# DISPLAY.net
KiCad netlist of a schematic drawn in Altium Designer
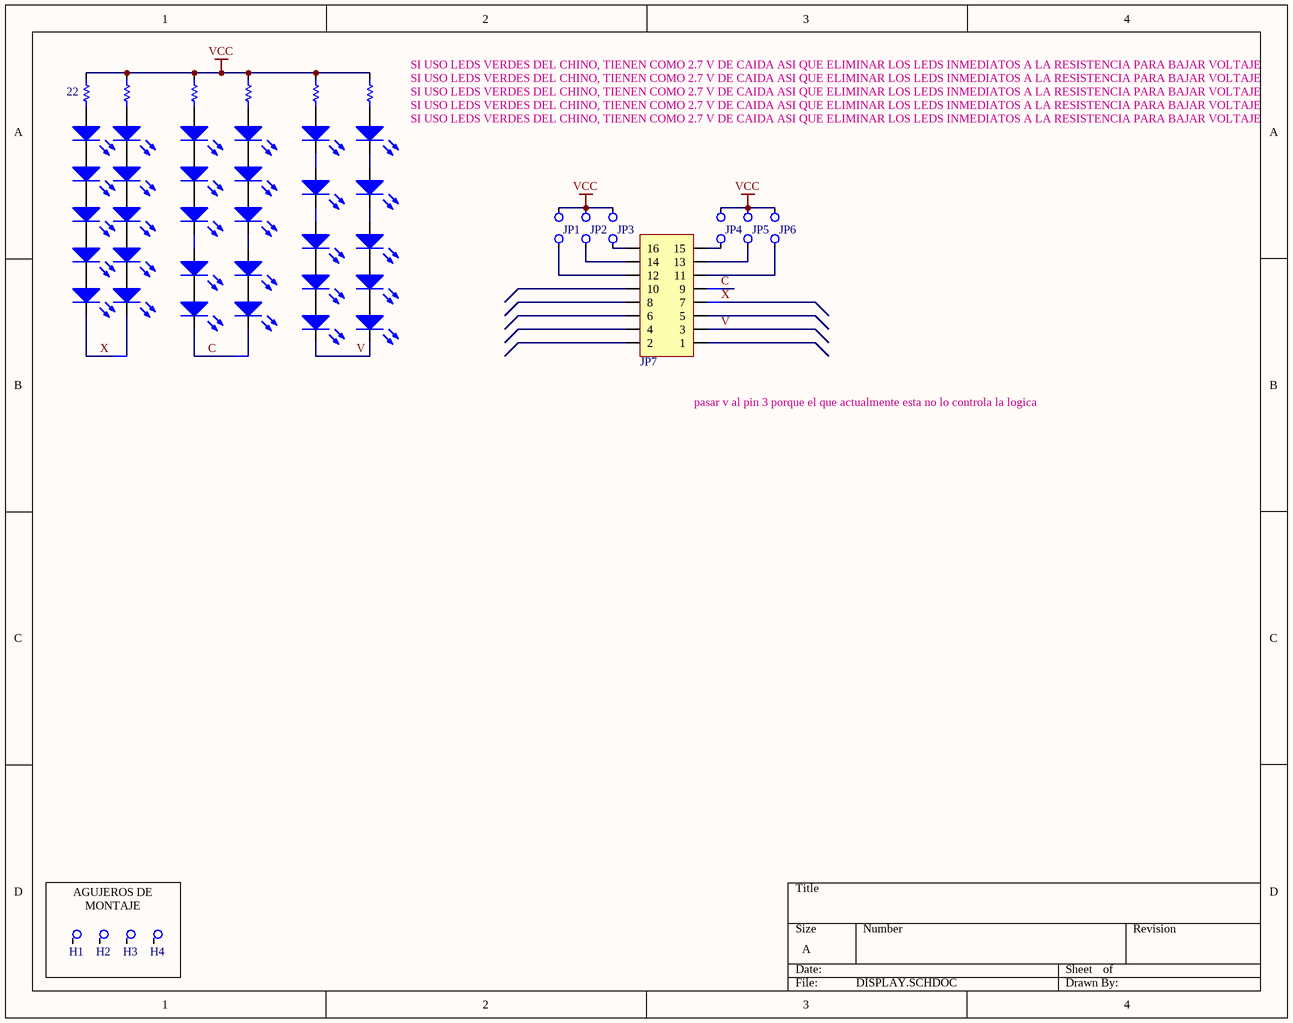
[diagram p0: DISPLAY.SCHDOC]

(export (version "E")
  (design (tool "Eeschema 10.0.6"))
  (components
    (comp (ref "D1")
      (value "LED")
      (footprint "LED5MM rojo")
      (description "Led")
      (libsource (lib "FEDE") (part "LED"))
    )
    (comp (ref "D2")
      (value "LED")
      (footprint "LED5MM rojo")
      (description "Led")
      (libsource (lib "FEDE") (part "LED"))
    )
    (comp (ref "D3")
      (value "LED")
      (footprint "LED5MM verde")
      (description "Led")
      (libsource (lib "FEDE") (part "LED"))
    )
    (comp (ref "D7")
      (value "LED")
      (footprint "LED5MM yellow")
      (description "Led")
      (libsource (lib "FEDE") (part "LED"))
    )
    (comp (ref "D8")
      (value "LED")
      (footprint "LED5MM verde")
      (description "Led")
      (libsource (lib "FEDE") (part "LED"))
    )
    (comp (ref "D9")
      (value "LED")
      (footprint "LED5MM yellow")
      (description "Led")
      (libsource (lib "FEDE") (part "LED"))
    )
    (comp (ref "D11")
      (value "LED")
      (footprint "LED5MM rojo")
      (description "Led")
      (libsource (lib "FEDE") (part "LED"))
    )
    (comp (ref "D12")
      (value "LED")
      (footprint "LED5MM rojo")
      (description "Led")
      (libsource (lib "FEDE") (part "LED"))
    )
    (comp (ref "D13")
      (value "LED")
      (footprint "LED5MM verde")
      (description "Led")
      (libsource (lib "FEDE") (part "LED"))
    )
    (comp (ref "D17")
      (value "LED")
      (footprint "LED5MM yellow")
      (description "Led")
      (libsource (lib "FEDE") (part "LED"))
    )
    (comp (ref "D18")
      (value "LED")
      (footprint "LED5MM verde")
      (description "Led")
      (libsource (lib "FEDE") (part "LED"))
    )
    (comp (ref "D19")
      (value "LED")
      (footprint "LED5MM yellow")
      (description "Led")
      (libsource (lib "FEDE") (part "LED"))
    )
    (comp (ref "D21")
      (value "LED")
      (footprint "LED5MM rojo")
      (description "Led")
      (libsource (lib "FEDE") (part "LED"))
    )
    (comp (ref "D22")
      (value "LED")
      (footprint "LED5MM rojo")
      (description "Led")
      (libsource (lib "FEDE") (part "LED"))
    )
    (comp (ref "D23")
      (value "LED")
      (footprint "LED5MM verde")
      (description "Led")
      (libsource (lib "FEDE") (part "LED"))
    )
    (comp (ref "D27")
      (value "LED")
      (footprint "LED5MM yellow")
      (description "Led")
      (libsource (lib "FEDE") (part "LED"))
    )
    (comp (ref "D28")
      (value "LED")
      (footprint "LED5MM verde")
      (description "Led")
      (libsource (lib "FEDE") (part "LED"))
    )
    (comp (ref "D29")
      (value "LED")
      (footprint "LED5MM yellow")
      (description "Led")
      (libsource (lib "FEDE") (part "LED"))
    )
    (comp (ref "D31")
      (value "LED")
      (footprint "LED5MM rojo")
      (description "Led")
      (libsource (lib "FEDE") (part "LED"))
    )
    (comp (ref "D32")
      (value "LED")
      (footprint "LED5MM rojo")
      (description "Led")
      (libsource (lib "FEDE") (part "LED"))
    )
    (comp (ref "D33")
      (value "LED")
      (footprint "LED5MM verde")
      (description "Led")
      (libsource (lib "FEDE") (part "LED"))
    )
    (comp (ref "D37")
      (value "LED")
      (footprint "LED5MM yellow")
      (description "Led")
      (libsource (lib "FEDE") (part "LED"))
    )
    (comp (ref "D38")
      (value "LED")
      (footprint "LED5MM verde")
      (description "Led")
      (libsource (lib "FEDE") (part "LED"))
    )
    (comp (ref "D39")
      (value "LED")
      (footprint "LED5MM yellow")
      (description "Led")
      (libsource (lib "FEDE") (part "LED"))
    )
    (comp (ref "D41")
      (value "LED")
      (footprint "LED5MM rojo")
      (description "Led")
      (libsource (lib "FEDE") (part "LED"))
    )
    (comp (ref "D42")
      (value "LED")
      (footprint "LED5MM rojo")
      (description "Led")
      (libsource (lib "FEDE") (part "LED"))
    )
    (comp (ref "D43")
      (value "LED")
      (footprint "LED5MM verde")
      (description "Led")
      (libsource (lib "FEDE") (part "LED"))
    )
    (comp (ref "D47")
      (value "LED")
      (footprint "LED5MM yellow")
      (description "Led")
      (libsource (lib "FEDE") (part "LED"))
    )
    (comp (ref "D48")
      (value "LED")
      (footprint "LED5MM verde")
      (description "Led")
      (libsource (lib "FEDE") (part "LED"))
    )
    (comp (ref "D49")
      (value "LED")
      (footprint "LED5MM yellow")
      (description "Led")
      (libsource (lib "FEDE") (part "LED"))
    )
    (comp (ref "H1")
      (value "Agujero de montaje")
      (footprint "agujero")
      (libsource (lib "FEDE") (part "Agujero de montaje"))
    )
    (comp (ref "H2")
      (value "Agujero de montaje")
      (footprint "agujero")
      (libsource (lib "FEDE") (part "Agujero de montaje"))
    )
    (comp (ref "H3")
      (value "Agujero de montaje")
      (footprint "agujero")
      (libsource (lib "FEDE") (part "Agujero de montaje"))
    )
    (comp (ref "H4")
      (value "Agujero de montaje")
      (footprint "agujero")
      (libsource (lib "FEDE") (part "Agujero de montaje"))
    )
    (comp (ref "JP1")
      (value "JP")
      (footprint "JUMPER2")
      (description "Jumper 2 contactos")
      (libsource (lib "FEDE") (part "JP"))
    )
    (comp (ref "JP2")
      (value "JP")
      (footprint "JUMPER2")
      (description "Jumper 2 contactos")
      (libsource (lib "FEDE") (part "JP"))
    )
    (comp (ref "JP3")
      (value "JP")
      (footprint "JUMPER2")
      (description "Jumper 2 contactos")
      (libsource (lib "FEDE") (part "JP"))
    )
    (comp (ref "JP4")
      (value "JP")
      (footprint "JUMPER2")
      (description "Jumper 2 contactos")
      (libsource (lib "FEDE") (part "JP"))
    )
    (comp (ref "JP5")
      (value "JP")
      (footprint "JUMPER2")
      (description "Jumper 2 contactos")
      (libsource (lib "FEDE") (part "JP"))
    )
    (comp (ref "JP6")
      (value "JP")
      (footprint "JUMPER2")
      (description "Jumper 2 contactos")
      (libsource (lib "FEDE") (part "JP"))
    )
    (comp (ref "JP7")
      (value "Header8x2")
      (footprint "IDC8x2_90")
      (description "Header 8x2")
      (libsource (lib "FEDE") (part "Header8x2"))
    )
    (comp (ref "R1")
      (value "22")
      (footprint "r1206")
      (description "Resistor")
      (fields (field (name "POWER") "0.25W") (field (name "Comment") "Res"))
      (libsource (lib "FEDE") (part "Res"))
    )
    (comp (ref "R2")
      (value "Res")
      (footprint "r1206")
      (description "Resistor")
      (fields (field (name "POWER") "0.25W"))
      (libsource (lib "FEDE") (part "Res"))
    )
    (comp (ref "R3")
      (value "Res")
      (footprint "r1206")
      (description "Resistor")
      (fields (field (name "POWER") "0.25W"))
      (libsource (lib "FEDE") (part "Res"))
    )
    (comp (ref "R7")
      (value "Res")
      (footprint "r1206")
      (description "Resistor")
      (fields (field (name "POWER") "0.25W"))
      (libsource (lib "FEDE") (part "Res"))
    )
    (comp (ref "R8")
      (value "Res")
      (footprint "r1206")
      (description "Resistor")
      (fields (field (name "POWER") "0.25W"))
      (libsource (lib "FEDE") (part "Res"))
    )
    (comp (ref "R9")
      (value "Res")
      (footprint "r1206")
      (description "Resistor")
      (fields (field (name "POWER") "0.25W"))
      (libsource (lib "FEDE") (part "Res"))
    )
    (comp (ref "W1")
      (value "CABLE")
      (footprint "r1206")
      (description "Cable")
      (libsource (lib "FEDE") (part "CABLE"))
    )
    (comp (ref "W2")
      (value "CABLE")
      (footprint "r1206")
      (description "Cable")
      (libsource (lib "FEDE") (part "CABLE"))
    )
    (comp (ref "W3")
      (value "CABLE")
      (footprint "r1206")
      (description "Cable")
      (libsource (lib "FEDE") (part "CABLE"))
    )
    (comp (ref "W4")
      (value "CABLE")
      (footprint "r1206")
      (description "Cable")
      (libsource (lib "FEDE") (part "CABLE"))
    )
    (comp (ref "W5")
      (value "CABLE")
      (footprint "r1206")
      (description "Cable")
      (libsource (lib "FEDE") (part "CABLE"))
    )
    (comp (ref "W6")
      (value "CABLE")
      (footprint "r1206")
      (description "Cable")
      (libsource (lib "FEDE") (part "CABLE"))
    )
    (comp (ref "W7")
      (value "CABLE")
      (footprint "r1206")
      (description "Cable")
      (libsource (lib "FEDE") (part "CABLE"))
    )
  )
  (nets
    (net (code "1") (name "/C") (class "Default")
      (node (ref "D47") (pin "2") (pinfunction "K_2") (pintype "passive"))
      (node (ref "W2") (pin "1") (pinfunction "1_1") (pintype "passive"))
      (node (ref "W6") (pin "2") (pinfunction "2_2") (pintype "passive"))
    )
    (net (code "2") (name "/V") (class "Default")
      (node (ref "D3") (pin "2") (pinfunction "K_2") (pintype "passive"))
      (node (ref "D48") (pin "2") (pinfunction "K_2") (pintype "passive"))
      (node (ref "JP7") (pin "3") (pinfunction "3_3") (pintype "passive"))
    )
    (net (code "3") (name "/X") (class "Default")
      (node (ref "D41") (pin "2") (pinfunction "K_2") (pintype "passive"))
      (node (ref "W5") (pin "1") (pinfunction "1_1") (pintype "passive"))
      (node (ref "W7") (pin "2") (pinfunction "2_2") (pintype "passive"))
    )
    (net (code "4") (name "Net-(D1-A)") (class "Default")
      (node (ref "D1") (pin "1") (pinfunction "A_1") (pintype "passive"))
      (node (ref "R1") (pin "1") (pinfunction "1_1") (pintype "passive"))
    )
    (net (code "5") (name "Net-(D1-K)") (class "Default")
      (node (ref "D1") (pin "2") (pinfunction "K_2") (pintype "passive"))
      (node (ref "D11") (pin "1") (pinfunction "A_1") (pintype "passive"))
    )
    (net (code "6") (name "Net-(D2-A)") (class "Default")
      (node (ref "D2") (pin "1") (pinfunction "A_1") (pintype "passive"))
      (node (ref "R2") (pin "1") (pinfunction "1_1") (pintype "passive"))
    )
    (net (code "7") (name "Net-(D7-A)") (class "Default")
      (node (ref "D7") (pin "1") (pinfunction "A_1") (pintype "passive"))
      (node (ref "R7") (pin "1") (pinfunction "1_1") (pintype "passive"))
    )
    (net (code "8") (name "Net-(D8-A)") (class "Default")
      (node (ref "D8") (pin "1") (pinfunction "A_1") (pintype "passive"))
      (node (ref "R8") (pin "1") (pinfunction "1_1") (pintype "passive"))
    )
    (net (code "9") (name "Net-(D9-A)") (class "Default")
      (node (ref "D9") (pin "1") (pinfunction "A_1") (pintype "passive"))
      (node (ref "R9") (pin "1") (pinfunction "1_1") (pintype "passive"))
    )
    (net (code "10") (name "Net-(D11-K)") (class "Default")
      (node (ref "D11") (pin "2") (pinfunction "K_2") (pintype "passive"))
      (node (ref "D21") (pin "1") (pinfunction "A_1") (pintype "passive"))
    )
    (net (code "11") (name "Net-(D12-A)") (class "Default")
      (node (ref "D12") (pin "1") (pinfunction "A_1") (pintype "passive"))
      (node (ref "D2") (pin "2") (pinfunction "K_2") (pintype "passive"))
    )
    (net (code "12") (name "Net-(D12-K)") (class "Default")
      (node (ref "D12") (pin "2") (pinfunction "K_2") (pintype "passive"))
      (node (ref "D22") (pin "1") (pinfunction "A_1") (pintype "passive"))
    )
    (net (code "13") (name "Net-(D13-A)") (class "Default")
      (node (ref "D13") (pin "1") (pinfunction "A_1") (pintype "passive"))
      (node (ref "D23") (pin "2") (pinfunction "K_2") (pintype "passive"))
    )
    (net (code "14") (name "Net-(D13-K)") (class "Default")
      (node (ref "D13") (pin "2") (pinfunction "K_2") (pintype "passive"))
      (node (ref "D3") (pin "1") (pinfunction "A_1") (pintype "passive"))
    )
    (net (code "15") (name "Net-(D17-A)") (class "Default")
      (node (ref "D17") (pin "1") (pinfunction "A_1") (pintype "passive"))
      (node (ref "D7") (pin "2") (pinfunction "K_2") (pintype "passive"))
    )
    (net (code "16") (name "Net-(D17-K)") (class "Default")
      (node (ref "D17") (pin "2") (pinfunction "K_2") (pintype "passive"))
      (node (ref "D27") (pin "1") (pinfunction "A_1") (pintype "passive"))
    )
    (net (code "17") (name "Net-(D18-A)") (class "Default")
      (node (ref "D18") (pin "1") (pinfunction "A_1") (pintype "passive"))
      (node (ref "D8") (pin "2") (pinfunction "K_2") (pintype "passive"))
    )
    (net (code "18") (name "Net-(D18-K)") (class "Default")
      (node (ref "D18") (pin "2") (pinfunction "K_2") (pintype "passive"))
      (node (ref "D28") (pin "1") (pinfunction "A_1") (pintype "passive"))
    )
    (net (code "19") (name "Net-(D19-A)") (class "Default")
      (node (ref "D19") (pin "1") (pinfunction "A_1") (pintype "passive"))
      (node (ref "D9") (pin "2") (pinfunction "K_2") (pintype "passive"))
    )
    (net (code "20") (name "Net-(D19-K)") (class "Default")
      (node (ref "D19") (pin "2") (pinfunction "K_2") (pintype "passive"))
      (node (ref "D29") (pin "1") (pinfunction "A_1") (pintype "passive"))
    )
    (net (code "21") (name "Net-(D21-K)") (class "Default")
      (node (ref "D21") (pin "2") (pinfunction "K_2") (pintype "passive"))
      (node (ref "D31") (pin "1") (pinfunction "A_1") (pintype "passive"))
    )
    (net (code "22") (name "Net-(D22-K)") (class "Default")
      (node (ref "D22") (pin "2") (pinfunction "K_2") (pintype "passive"))
      (node (ref "D32") (pin "1") (pinfunction "A_1") (pintype "passive"))
    )
    (net (code "23") (name "Net-(D23-A)") (class "Default")
      (node (ref "D23") (pin "1") (pinfunction "A_1") (pintype "passive"))
      (node (ref "W3") (pin "1") (pinfunction "1_1") (pintype "passive"))
    )
    (net (code "24") (name "Net-(D27-K)") (class "Default")
      (node (ref "D27") (pin "2") (pinfunction "K_2") (pintype "passive"))
      (node (ref "D37") (pin "1") (pinfunction "A_1") (pintype "passive"))
    )
    (net (code "25") (name "Net-(D28-K)") (class "Default")
      (node (ref "D28") (pin "2") (pinfunction "K_2") (pintype "passive"))
      (node (ref "D38") (pin "1") (pinfunction "A_1") (pintype "passive"))
    )
    (net (code "26") (name "Net-(D29-K)") (class "Default")
      (node (ref "D29") (pin "2") (pinfunction "K_2") (pintype "passive"))
      (node (ref "W1") (pin "2") (pinfunction "2_2") (pintype "passive"))
    )
    (net (code "27") (name "Net-(D31-K)") (class "Default")
      (node (ref "D31") (pin "2") (pinfunction "K_2") (pintype "passive"))
      (node (ref "D41") (pin "1") (pinfunction "A_1") (pintype "passive"))
    )
    (net (code "28") (name "Net-(D32-K)") (class "Default")
      (node (ref "D32") (pin "2") (pinfunction "K_2") (pintype "passive"))
      (node (ref "D42") (pin "1") (pinfunction "A_1") (pintype "passive"))
    )
    (net (code "29") (name "Net-(D33-A)") (class "Default")
      (node (ref "D33") (pin "1") (pinfunction "A_1") (pintype "passive"))
      (node (ref "W4") (pin "1") (pinfunction "1_1") (pintype "passive"))
    )
    (net (code "30") (name "Net-(D33-K)") (class "Default")
      (node (ref "D33") (pin "2") (pinfunction "K_2") (pintype "passive"))
      (node (ref "W3") (pin "2") (pinfunction "2_2") (pintype "passive"))
    )
    (net (code "31") (name "Net-(D37-K)") (class "Default")
      (node (ref "D37") (pin "2") (pinfunction "K_2") (pintype "passive"))
      (node (ref "D49") (pin "1") (pinfunction "A_1") (pintype "passive"))
    )
    (net (code "32") (name "Net-(D38-K)") (class "Default")
      (node (ref "D38") (pin "2") (pinfunction "K_2") (pintype "passive"))
      (node (ref "D48") (pin "1") (pinfunction "A_1") (pintype "passive"))
    )
    (net (code "33") (name "Net-(D39-A)") (class "Default")
      (node (ref "D39") (pin "1") (pinfunction "A_1") (pintype "passive"))
      (node (ref "W1") (pin "1") (pinfunction "1_1") (pintype "passive"))
    )
    (net (code "34") (name "Net-(D39-K)") (class "Default")
      (node (ref "D39") (pin "2") (pinfunction "K_2") (pintype "passive"))
      (node (ref "D47") (pin "1") (pinfunction "A_1") (pintype "passive"))
    )
    (net (code "35") (name "Net-(D42-K)") (class "Default")
      (node (ref "D42") (pin "2") (pinfunction "K_2") (pintype "passive"))
      (node (ref "W5") (pin "2") (pinfunction "2_2") (pintype "passive"))
    )
    (net (code "36") (name "Net-(D43-A)") (class "Default")
      (node (ref "D43") (pin "1") (pinfunction "A_1") (pintype "passive"))
      (node (ref "R3") (pin "1") (pinfunction "1_1") (pintype "passive"))
    )
    (net (code "37") (name "Net-(D43-K)") (class "Default")
      (node (ref "D43") (pin "2") (pinfunction "K_2") (pintype "passive"))
      (node (ref "W4") (pin "2") (pinfunction "2_2") (pintype "passive"))
    )
    (net (code "38") (name "Net-(D49-K)") (class "Default")
      (node (ref "D49") (pin "2") (pinfunction "K_2") (pintype "passive"))
      (node (ref "W2") (pin "2") (pinfunction "2_2") (pintype "passive"))
    )
    (net (code "39") (name "Net-(JP1-Pad1)") (class "Default")
      (node (ref "JP1") (pin "1") (pinfunction "1_1") (pintype "passive"))
      (node (ref "JP7") (pin "12") (pinfunction "12_12") (pintype "passive"))
    )
    (net (code "40") (name "Net-(JP2-Pad1)") (class "Default")
      (node (ref "JP2") (pin "1") (pinfunction "1_1") (pintype "passive"))
      (node (ref "JP7") (pin "14") (pinfunction "14_14") (pintype "passive"))
    )
    (net (code "41") (name "Net-(JP3-Pad1)") (class "Default")
      (node (ref "JP3") (pin "1") (pinfunction "1_1") (pintype "passive"))
      (node (ref "JP7") (pin "16") (pinfunction "16_16") (pintype "passive"))
    )
    (net (code "42") (name "Net-(JP4-Pad1)") (class "Default")
      (node (ref "JP4") (pin "1") (pinfunction "1_1") (pintype "passive"))
      (node (ref "JP7") (pin "15") (pinfunction "15_15") (pintype "passive"))
    )
    (net (code "43") (name "Net-(JP5-Pad1)") (class "Default")
      (node (ref "JP5") (pin "1") (pinfunction "1_1") (pintype "passive"))
      (node (ref "JP7") (pin "13") (pinfunction "13_13") (pintype "passive"))
    )
    (net (code "44") (name "Net-(JP6-Pad1)") (class "Default")
      (node (ref "JP6") (pin "1") (pinfunction "1_1") (pintype "passive"))
      (node (ref "JP7") (pin "11") (pinfunction "11_11") (pintype "passive"))
    )
    (net (code "45") (name "Net-(JP7-Pad7)") (class "Default")
      (node (ref "JP7") (pin "7") (pinfunction "7_7") (pintype "passive"))
      (node (ref "W7") (pin "1") (pinfunction "1_1") (pintype "passive"))
    )
    (net (code "46") (name "Net-(JP7-Pad9)") (class "Default")
      (node (ref "JP7") (pin "9") (pinfunction "9_9") (pintype "passive"))
      (node (ref "W6") (pin "1") (pinfunction "1_1") (pintype "passive"))
    )
    (net (code "47") (name "VCC") (class "Default")
      (node (ref "JP1") (pin "2") (pinfunction "2_2") (pintype "passive"))
      (node (ref "JP2") (pin "2") (pinfunction "2_2") (pintype "passive"))
      (node (ref "JP3") (pin "2") (pinfunction "2_2") (pintype "passive"))
      (node (ref "JP4") (pin "2") (pinfunction "2_2") (pintype "passive"))
      (node (ref "JP5") (pin "2") (pinfunction "2_2") (pintype "passive"))
      (node (ref "JP6") (pin "2") (pinfunction "2_2") (pintype "passive"))
      (node (ref "R1") (pin "2") (pinfunction "2_2") (pintype "passive"))
      (node (ref "R2") (pin "2") (pinfunction "2_2") (pintype "passive"))
      (node (ref "R3") (pin "2") (pinfunction "2_2") (pintype "passive"))
      (node (ref "R7") (pin "2") (pinfunction "2_2") (pintype "passive"))
      (node (ref "R8") (pin "2") (pinfunction "2_2") (pintype "passive"))
      (node (ref "R9") (pin "2") (pinfunction "2_2") (pintype "passive"))
    )
    (net (code "48") (name "unconnected-(H1-Pad1)") (class "Default")
      (node (ref "H1") (pin "1") (pinfunction "1_1") (pintype "passive"))
    )
    (net (code "49") (name "unconnected-(H2-Pad1)") (class "Default")
      (node (ref "H2") (pin "1") (pinfunction "1_1") (pintype "passive"))
    )
    (net (code "50") (name "unconnected-(H3-Pad1)") (class "Default")
      (node (ref "H3") (pin "1") (pinfunction "1_1") (pintype "passive"))
    )
    (net (code "51") (name "unconnected-(H4-Pad1)") (class "Default")
      (node (ref "H4") (pin "1") (pinfunction "1_1") (pintype "passive"))
    )
    (net (code "52") (name "unconnected-(JP7-Pad1)") (class "Default")
      (node (ref "JP7") (pin "1") (pinfunction "1_1") (pintype "passive"))
    )
    (net (code "53") (name "unconnected-(JP7-Pad2)") (class "Default")
      (node (ref "JP7") (pin "2") (pinfunction "2_2") (pintype "passive"))
    )
    (net (code "54") (name "unconnected-(JP7-Pad4)") (class "Default")
      (node (ref "JP7") (pin "4") (pinfunction "4_4") (pintype "passive"))
    )
    (net (code "55") (name "unconnected-(JP7-Pad5)") (class "Default")
      (node (ref "JP7") (pin "5") (pinfunction "5_5") (pintype "passive"))
    )
    (net (code "56") (name "unconnected-(JP7-Pad6)") (class "Default")
      (node (ref "JP7") (pin "6") (pinfunction "6_6") (pintype "passive"))
    )
    (net (code "57") (name "unconnected-(JP7-Pad8)") (class "Default")
      (node (ref "JP7") (pin "8") (pinfunction "8_8") (pintype "passive"))
    )
    (net (code "58") (name "unconnected-(JP7-Pad10)") (class "Default")
      (node (ref "JP7") (pin "10") (pinfunction "10_10") (pintype "passive"))
    )
  )
)
